# MRF49XA.net
KiCad netlist of a schematic drawn in EAGLE
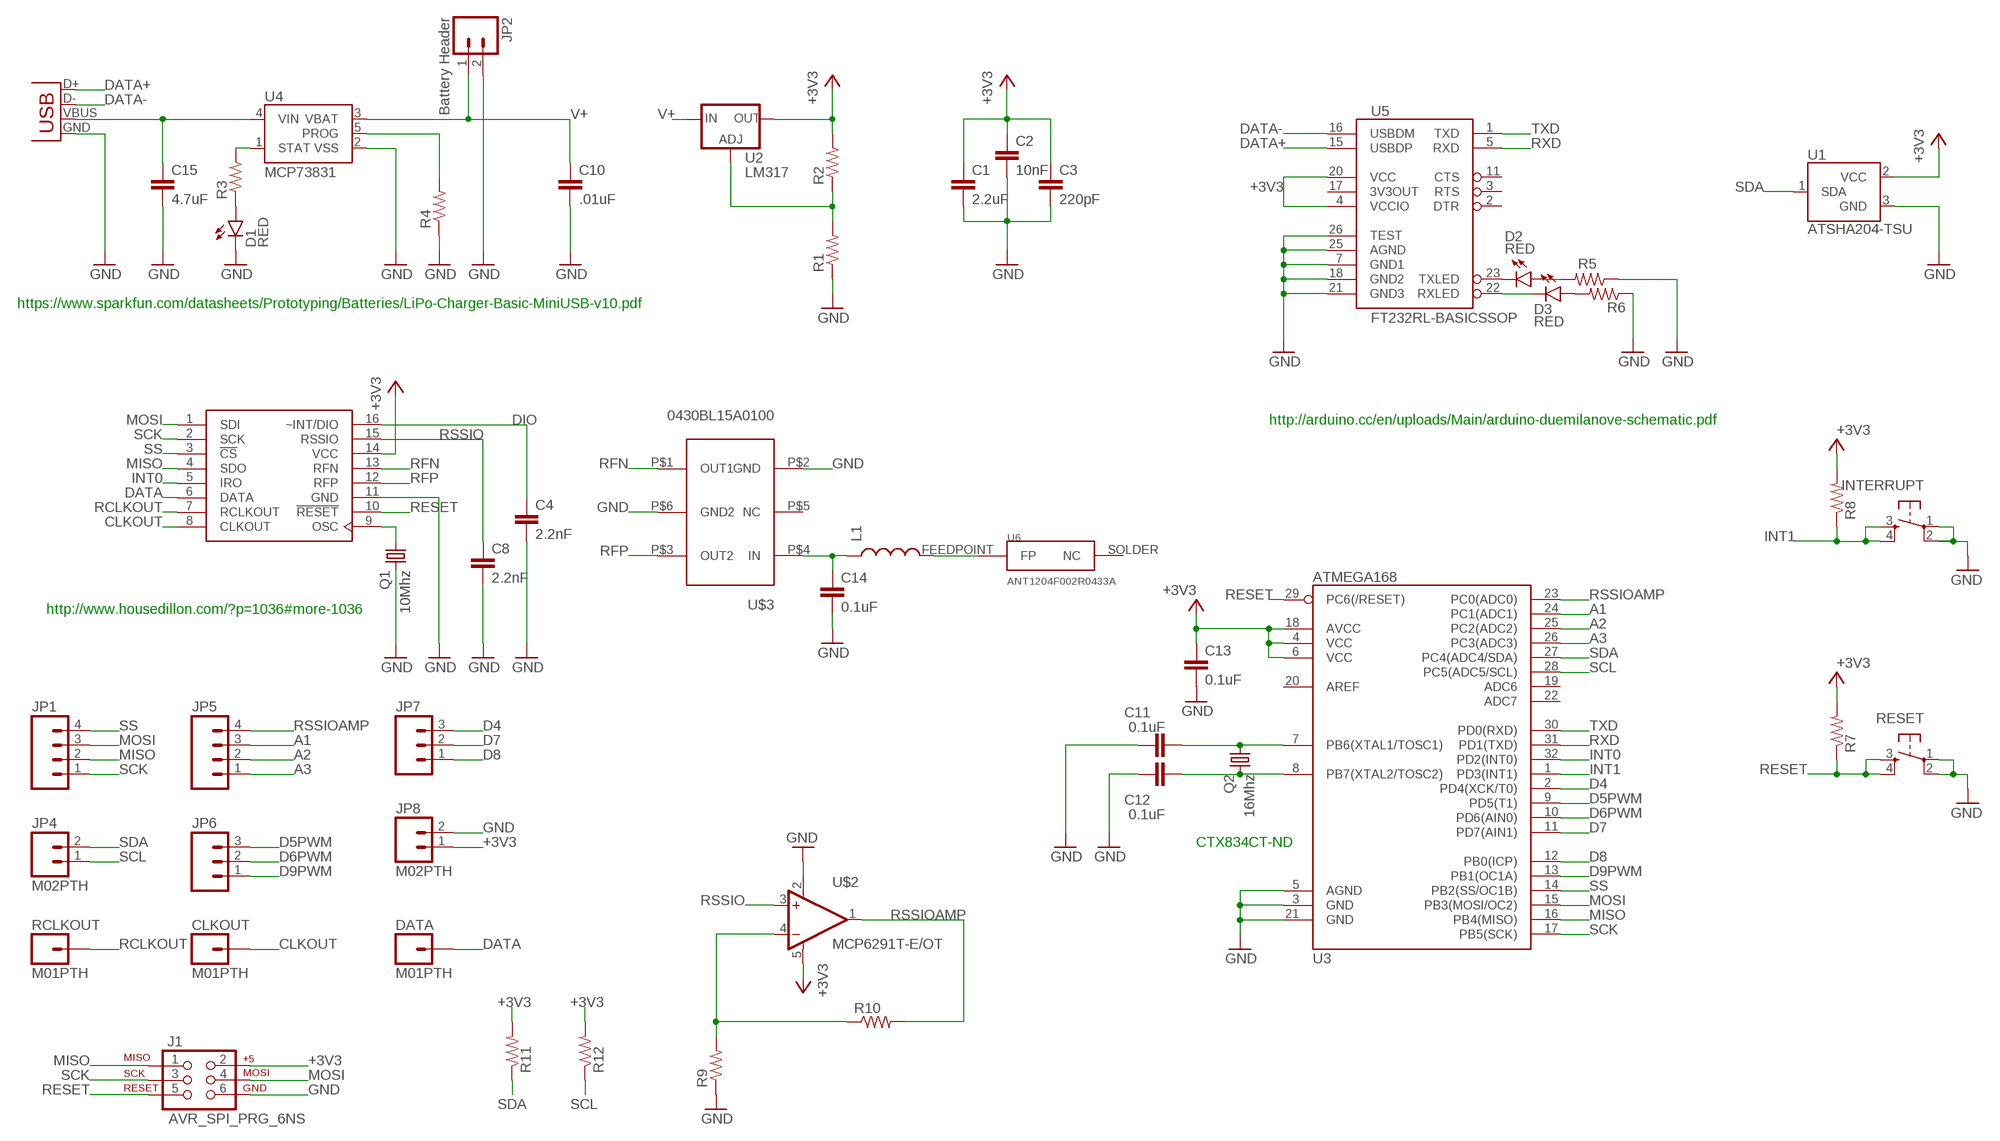
[diagram p0: schematic, sheet 1]

(export (version "E")
  (design (tool "Eeschema 10.0.6"))
  (components
    (comp (ref "C1")
      (value "2.2uF")
      (footprint "eagle-import:C3216")
      (libsource (lib "eagle-import") (part "C-EUC3216"))
    )
    (comp (ref "C2")
      (value "10nF")
      (footprint "eagle-import:C0603K")
      (libsource (lib "eagle-import") (part "C-EUC0603K"))
    )
    (comp (ref "C3")
      (value "220pF")
      (footprint "eagle-import:C0603")
      (libsource (lib "eagle-import") (part "C-EUC0603"))
    )
    (comp (ref "C4")
      (value "2.2nF")
      (footprint "eagle-import:C0603K")
      (libsource (lib "eagle-import") (part "C-EUC0603K"))
    )
    (comp (ref "C8")
      (value "2.2nF")
      (footprint "eagle-import:C0603K")
      (libsource (lib "eagle-import") (part "C-EUC0603K"))
    )
    (comp (ref "C10")
      (value ".01uF")
      (footprint "eagle-import:C3216")
      (libsource (lib "eagle-import") (part "C-EUC3216"))
    )
    (comp (ref "C11")
      (value "0.1uF")
      (footprint "eagle-import:0603-CAP")
      (libsource (lib "eagle-import") (part "0.1UF-25V-5%(0603)"))
    )
    (comp (ref "C12")
      (value "0.1uF")
      (footprint "eagle-import:0603-CAP")
      (libsource (lib "eagle-import") (part "0.1UF-25V-5%(0603)"))
    )
    (comp (ref "C13")
      (value "0.1uF")
      (footprint "eagle-import:0603-CAP")
      (libsource (lib "eagle-import") (part "0.1UF-25V-5%(0603)"))
    )
    (comp (ref "C14")
      (value "0.1uF")
      (footprint "eagle-import:0603-CAP")
      (libsource (lib "eagle-import") (part "0.1UF-25V-5%(0603)"))
    )
    (comp (ref "C15")
      (value "4.7uF")
      (footprint "eagle-import:C3216")
      (libsource (lib "eagle-import") (part "C-EUC3216"))
    )
    (comp (ref "CLKOUT")
      (value "M01PTH")
      (footprint "eagle-import:1X01")
      (libsource (lib "eagle-import") (part "M01PTH"))
    )
    (comp (ref "D1")
      (value "RED")
      (footprint "eagle-import:LED-0603")
      (libsource (lib "eagle-import") (part "LED-RED0603"))
    )
    (comp (ref "D2")
      (value "RED")
      (footprint "eagle-import:LED-0603")
      (libsource (lib "eagle-import") (part "LED-RED0603"))
    )
    (comp (ref "D3")
      (value "RED")
      (footprint "eagle-import:LED-0603")
      (libsource (lib "eagle-import") (part "LED-RED0603"))
    )
    (comp (ref "DATA")
      (value "M01PTH")
      (footprint "eagle-import:1X01")
      (libsource (lib "eagle-import") (part "M01PTH"))
    )
    (comp (ref "INTERRUPT")
      (value "TAC_SWITCHSMD")
      (footprint "eagle-import:TACTILE-SWITCH-SMD")
      (libsource (lib "eagle-import") (part "TAC_SWITCHSMD"))
    )
    (comp (ref "J1")
      (value "AVR_SPI_PRG_6NS")
      (footprint "eagle-import:2X3-NS")
      (libsource (lib "eagle-import") (part "AVR_SPI_PRG_6NS"))
    )
    (comp (ref "JP1")
      (value "M04PTH")
      (footprint "eagle-import:1X04")
      (libsource (lib "eagle-import") (part "M04PTH"))
    )
    (comp (ref "JP2")
      (value "Battery Header")
      (footprint "eagle-import:1X02_LOCK_LONGPADS")
      (libsource (lib "eagle-import") (part "M02LOCK_LONGPADS"))
    )
    (comp (ref "JP3")
      (value "USBSMD")
      (footprint "eagle-import:USB-MINIB")
      (libsource (lib "eagle-import") (part "USBSMD"))
    )
    (comp (ref "JP4")
      (value "M02PTH")
      (footprint "eagle-import:1X02")
      (libsource (lib "eagle-import") (part "M02PTH"))
    )
    (comp (ref "JP5")
      (value "M04PTH")
      (footprint "eagle-import:1X04")
      (libsource (lib "eagle-import") (part "M04PTH"))
    )
    (comp (ref "JP6")
      (value "M03PTH")
      (footprint "eagle-import:1X03")
      (libsource (lib "eagle-import") (part "M03PTH"))
    )
    (comp (ref "JP7")
      (value "M03PTH")
      (footprint "eagle-import:1X03")
      (libsource (lib "eagle-import") (part "M03PTH"))
    )
    (comp (ref "JP8")
      (value "M02PTH")
      (footprint "eagle-import:1X02")
      (libsource (lib "eagle-import") (part "M02PTH"))
    )
    (comp (ref "L1")
      (value "INDUCTOR0603")
      (footprint "eagle-import:0603")
      (libsource (lib "eagle-import") (part "INDUCTOR0603"))
    )
    (comp (ref "Q1")
      (value "10Mhz")
      (footprint "eagle-import:CTS406")
      (libsource (lib "eagle-import") (part "CRYSTALCTS406"))
    )
    (comp (ref "Q2")
      (value "16Mhz")
      (footprint "eagle-import:CTS406")
      (libsource (lib "eagle-import") (part "CRYSTALCTS406"))
    )
    (comp (ref "R1")
      (value "R-US_R0603")
      (footprint "eagle-import:R0603")
      (libsource (lib "eagle-import") (part "R-US_R0603"))
    )
    (comp (ref "R2")
      (value "R-US_R0603")
      (footprint "eagle-import:R0603")
      (libsource (lib "eagle-import") (part "R-US_R0603"))
    )
    (comp (ref "R3")
      (value "RESISTOR0603-RES")
      (footprint "eagle-import:0603-RES")
      (libsource (lib "eagle-import") (part "RESISTOR0603-RES"))
    )
    (comp (ref "R4")
      (value "RESISTOR0603-RES")
      (footprint "eagle-import:0603-RES")
      (libsource (lib "eagle-import") (part "RESISTOR0603-RES"))
    )
    (comp (ref "R5")
      (value "R-US_R0603")
      (footprint "eagle-import:R0603")
      (libsource (lib "eagle-import") (part "R-US_R0603"))
    )
    (comp (ref "R6")
      (value "R-US_R0603")
      (footprint "eagle-import:R0603")
      (libsource (lib "eagle-import") (part "R-US_R0603"))
    )
    (comp (ref "R7")
      (value "R-US_R0603")
      (footprint "eagle-import:R0603")
      (libsource (lib "eagle-import") (part "R-US_R0603"))
    )
    (comp (ref "R8")
      (value "R-US_R0603")
      (footprint "eagle-import:R0603")
      (libsource (lib "eagle-import") (part "R-US_R0603"))
    )
    (comp (ref "R9")
      (value "RESISTOR0603-RES")
      (footprint "eagle-import:0603-RES")
      (libsource (lib "eagle-import") (part "RESISTOR0603-RES"))
    )
    (comp (ref "R10")
      (value "RESISTOR0603-RES")
      (footprint "eagle-import:0603-RES")
      (libsource (lib "eagle-import") (part "RESISTOR0603-RES"))
    )
    (comp (ref "R11")
      (value "R-US_R0603")
      (footprint "eagle-import:R0603")
      (libsource (lib "eagle-import") (part "R-US_R0603"))
    )
    (comp (ref "R12")
      (value "R-US_R0603")
      (footprint "eagle-import:R0603")
      (libsource (lib "eagle-import") (part "R-US_R0603"))
    )
    (comp (ref "RCLKOUT")
      (value "M01PTH")
      (footprint "eagle-import:1X01")
      (libsource (lib "eagle-import") (part "M01PTH"))
    )
    (comp (ref "RESET")
      (value "TAC_SWITCHSMD")
      (footprint "eagle-import:TACTILE-SWITCH-SMD")
      (libsource (lib "eagle-import") (part "TAC_SWITCHSMD"))
    )
    (comp (ref "U$1")
      (value "MRF49XA")
      (footprint "eagle-import:TSSOP16")
      (libsource (lib "eagle-import") (part "MRF49XA"))
    )
    (comp (ref "U$2")
      (value "MCP6291T-E/OT")
      (footprint "eagle-import:SOT23-5")
      (libsource (lib "eagle-import") (part "MCP6291T-E/OT"))
    )
    (comp (ref "U$3")
      (value "0430BL15A0100")
      (footprint "eagle-import:0430BL15A0100")
      (libsource (lib "eagle-import") (part "0430BL15A0100"))
    )
    (comp (ref "U1")
      (value "ATSHA204-TSU")
      (footprint "eagle-import:SOT23-3")
      (libsource (lib "eagle-import") (part "ATSHA204-TSU"))
    )
    (comp (ref "U2")
      (value "LM317")
      (footprint "eagle-import:SOT223")
      (libsource (lib "eagle-import") (part "V_REG_317SMD"))
    )
    (comp (ref "U3")
      (value "ATMEGA168")
      (footprint "eagle-import:TQFP32-08")
      (libsource (lib "eagle-import") (part "ATMEGA168"))
    )
    (comp (ref "U4")
      (value "MCP73831")
      (footprint "eagle-import:SOT23-5")
      (libsource (lib "eagle-import") (part "MCP73831"))
    )
    (comp (ref "U5")
      (value "FT232RL-BASICSSOP")
      (footprint "eagle-import:SSOP28DB")
      (libsource (lib "eagle-import") (part "FT232RL-BASICSSOP"))
    )
    (comp (ref "U6")
      (value "ANT1204F002R0433A")
      (footprint "eagle-import:ANT1204F002R0433A")
      (libsource (lib "eagle-import") (part "ANT1204F002R0433A"))
    )
  )
  (nets
    (net (code "1") (name "+3V3") (class "Default")
      (node (ref "C1") (pin "1") (pinfunction "1_1") (pintype "passive"))
      (node (ref "C13") (pin "1") (pinfunction "1_1") (pintype "passive"))
      (node (ref "C2") (pin "1") (pinfunction "1_1") (pintype "passive"))
      (node (ref "C3") (pin "1") (pinfunction "1_1") (pintype "passive"))
      (node (ref "J1") (pin "2") (pinfunction "2_2") (pintype "passive"))
      (node (ref "JP8") (pin "1") (pinfunction "1_1") (pintype "passive"))
      (node (ref "R11") (pin "2") (pinfunction "2_2") (pintype "passive"))
      (node (ref "R12") (pin "2") (pinfunction "2_2") (pintype "passive"))
      (node (ref "R2") (pin "2") (pinfunction "2_2") (pintype "passive"))
      (node (ref "R7") (pin "2") (pinfunction "2_2") (pintype "passive"))
      (node (ref "R8") (pin "2") (pinfunction "2_2") (pintype "passive"))
      (node (ref "U$1") (pin "14") (pinfunction "VCC_14") (pintype "bidirectional"))
      (node (ref "U$2") (pin "5") (pinfunction "V+_5") (pintype "power_in"))
      (node (ref "U1") (pin "2") (pinfunction "VCC_2") (pintype "bidirectional"))
      (node (ref "U2") (pin "2") (pinfunction "OUT_2") (pintype "output"))
      (node (ref "U3") (pin "18") (pinfunction "AVCC_18") (pintype "bidirectional"))
      (node (ref "U3") (pin "4") (pinfunction "VCC_4") (pintype "bidirectional"))
      (node (ref "U3") (pin "6") (pinfunction "VCC_6") (pintype "bidirectional"))
      (node (ref "U5") (pin "20") (pinfunction "VCC_20") (pintype "power_in"))
      (node (ref "U5") (pin "4") (pinfunction "VCCIO_4") (pintype "power_in"))
    )
    (net (code "2") (name "/A1") (class "Default")
      (node (ref "JP5") (pin "3") (pinfunction "3_3") (pintype "passive"))
      (node (ref "U3") (pin "24") (pinfunction "PC1(ADC1)_24") (pintype "bidirectional"))
    )
    (net (code "3") (name "/A2") (class "Default")
      (node (ref "JP5") (pin "2") (pinfunction "2_2") (pintype "passive"))
      (node (ref "U3") (pin "25") (pinfunction "PC2(ADC2)_25") (pintype "bidirectional"))
    )
    (net (code "4") (name "/A3") (class "Default")
      (node (ref "JP5") (pin "1") (pinfunction "1_1") (pintype "passive"))
      (node (ref "U3") (pin "26") (pinfunction "PC3(ADC3)_26") (pintype "bidirectional"))
    )
    (net (code "5") (name "/CLKOUT") (class "Default")
      (node (ref "CLKOUT") (pin "1") (pinfunction "1_1") (pintype "passive"))
      (node (ref "U$1") (pin "8") (pinfunction "CLKOUT_8") (pintype "output"))
    )
    (net (code "6") (name "/D4") (class "Default")
      (node (ref "JP7") (pin "3") (pinfunction "3_3") (pintype "passive"))
      (node (ref "U3") (pin "2") (pinfunction "PD4(XCK/T0)_2") (pintype "bidirectional"))
    )
    (net (code "7") (name "/D5PWM") (class "Default")
      (node (ref "JP6") (pin "3") (pinfunction "3_3") (pintype "passive"))
      (node (ref "U3") (pin "9") (pinfunction "PD5(T1)_9") (pintype "bidirectional"))
    )
    (net (code "8") (name "/D6PWM") (class "Default")
      (node (ref "JP6") (pin "2") (pinfunction "2_2") (pintype "passive"))
      (node (ref "U3") (pin "10") (pinfunction "PD6(AIN0)_10") (pintype "bidirectional"))
    )
    (net (code "9") (name "/D7") (class "Default")
      (node (ref "JP7") (pin "2") (pinfunction "2_2") (pintype "passive"))
      (node (ref "U3") (pin "11") (pinfunction "PD7(AIN1)_11") (pintype "bidirectional"))
    )
    (net (code "10") (name "/D8") (class "Default")
      (node (ref "JP7") (pin "1") (pinfunction "1_1") (pintype "passive"))
      (node (ref "U3") (pin "12") (pinfunction "PB0(ICP)_12") (pintype "bidirectional"))
    )
    (net (code "11") (name "/D9PWM") (class "Default")
      (node (ref "JP6") (pin "1") (pinfunction "1_1") (pintype "passive"))
      (node (ref "U3") (pin "13") (pinfunction "PB1(OC1A)_13") (pintype "bidirectional"))
    )
    (net (code "12") (name "/DATA") (class "Default")
      (node (ref "DATA") (pin "1") (pinfunction "1_1") (pintype "passive"))
      (node (ref "U$1") (pin "6") (pinfunction "DATA_6") (pintype "bidirectional"))
    )
    (net (code "13") (name "/DATA+") (class "Default")
      (node (ref "JP3") (pin "D+") (pinfunction "D+_D+") (pintype "bidirectional"))
      (node (ref "U5") (pin "15") (pinfunction "USBDP_15") (pintype "bidirectional"))
    )
    (net (code "14") (name "/DATA-") (class "Default")
      (node (ref "JP3") (pin "D-") (pinfunction "D-_D-") (pintype "bidirectional"))
      (node (ref "U5") (pin "16") (pinfunction "USBDM_16") (pintype "bidirectional"))
    )
    (net (code "15") (name "/DIO") (class "Default")
      (node (ref "C4") (pin "1") (pinfunction "1_1") (pintype "passive"))
      (node (ref "U$1") (pin "16") (pinfunction "~{INT/DIO}_16") (pintype "bidirectional"))
    )
    (net (code "16") (name "/INT0") (class "Default")
      (node (ref "U$1") (pin "5") (pinfunction "IRO_5") (pintype "output"))
      (node (ref "U3") (pin "32") (pinfunction "PD2(INT0)_32") (pintype "bidirectional"))
    )
    (net (code "17") (name "/INT1") (class "Default")
      (node (ref "INTERRUPT") (pin "3") (pinfunction "3_3") (pintype "passive"))
      (node (ref "INTERRUPT") (pin "4") (pinfunction "4_4") (pintype "passive"))
      (node (ref "R8") (pin "1") (pinfunction "1_1") (pintype "passive"))
      (node (ref "U3") (pin "1") (pinfunction "PD3(INT1)_1") (pintype "bidirectional"))
    )
    (net (code "18") (name "/MISO") (class "Default")
      (node (ref "J1") (pin "1") (pinfunction "1_1") (pintype "passive"))
      (node (ref "JP1") (pin "2") (pinfunction "2_2") (pintype "passive"))
      (node (ref "U$1") (pin "4") (pinfunction "SDO_4") (pintype "output"))
      (node (ref "U3") (pin "16") (pinfunction "PB4(MISO)_16") (pintype "bidirectional"))
    )
    (net (code "19") (name "/MOSI") (class "Default")
      (node (ref "J1") (pin "4") (pinfunction "4_4") (pintype "passive"))
      (node (ref "JP1") (pin "3") (pinfunction "3_3") (pintype "passive"))
      (node (ref "U$1") (pin "1") (pinfunction "SDI_1") (pintype "input"))
      (node (ref "U3") (pin "15") (pinfunction "PB3(MOSI/OC2)_15") (pintype "bidirectional"))
    )
    (net (code "20") (name "/RCLKOUT") (class "Default")
      (node (ref "RCLKOUT") (pin "1") (pinfunction "1_1") (pintype "passive"))
      (node (ref "U$1") (pin "7") (pinfunction "RCLKOUT_7") (pintype "bidirectional"))
    )
    (net (code "21") (name "/RESET") (class "Default")
      (node (ref "J1") (pin "5") (pinfunction "5_5") (pintype "passive"))
      (node (ref "R7") (pin "1") (pinfunction "1_1") (pintype "passive"))
      (node (ref "RESET") (pin "3") (pinfunction "3_3") (pintype "passive"))
      (node (ref "RESET") (pin "4") (pinfunction "4_4") (pintype "passive"))
      (node (ref "U$1") (pin "10") (pinfunction "~{RESET}_10") (pintype "bidirectional"))
      (node (ref "U3") (pin "29") (pinfunction "PC6(/RESET)_29") (pintype "bidirectional"))
    )
    (net (code "22") (name "/RFN") (class "Default")
      (node (ref "U$1") (pin "13") (pinfunction "RFN_13") (pintype "bidirectional"))
      (node (ref "U$3") (pin "P$1") (pinfunction "OUT1_P$1") (pintype "bidirectional"))
    )
    (net (code "23") (name "/RFP") (class "Default")
      (node (ref "U$1") (pin "12") (pinfunction "RFP_12") (pintype "bidirectional"))
      (node (ref "U$3") (pin "P$3") (pinfunction "OUT2_P$3") (pintype "bidirectional"))
    )
    (net (code "24") (name "/RSSIO") (class "Default")
      (node (ref "C8") (pin "1") (pinfunction "1_1") (pintype "passive"))
      (node (ref "U$1") (pin "15") (pinfunction "RSSIO_15") (pintype "bidirectional"))
      (node (ref "U$2") (pin "3") (pinfunction "+IN_3") (pintype "input"))
    )
    (net (code "25") (name "/RSSIOAMP") (class "Default")
      (node (ref "JP5") (pin "4") (pinfunction "4_4") (pintype "passive"))
      (node (ref "R10") (pin "2") (pinfunction "2_2") (pintype "passive"))
      (node (ref "U$2") (pin "1") (pinfunction "OUT_1") (pintype "output"))
      (node (ref "U3") (pin "23") (pinfunction "PC0(ADC0)_23") (pintype "bidirectional"))
    )
    (net (code "26") (name "/RXD") (class "Default")
      (node (ref "U3") (pin "31") (pinfunction "PD1(TXD)_31") (pintype "bidirectional"))
      (node (ref "U5") (pin "5") (pinfunction "RXD_5") (pintype "input"))
    )
    (net (code "27") (name "/SCK") (class "Default")
      (node (ref "J1") (pin "3") (pinfunction "3_3") (pintype "passive"))
      (node (ref "JP1") (pin "1") (pinfunction "1_1") (pintype "passive"))
      (node (ref "U$1") (pin "2") (pinfunction "SCK_2") (pintype "input"))
      (node (ref "U3") (pin "17") (pinfunction "PB5(SCK)_17") (pintype "bidirectional"))
    )
    (net (code "28") (name "/SCL") (class "Default")
      (node (ref "JP4") (pin "1") (pinfunction "1_1") (pintype "passive"))
      (node (ref "R12") (pin "1") (pinfunction "1_1") (pintype "passive"))
      (node (ref "U3") (pin "28") (pinfunction "PC5(ADC5/SCL)_28") (pintype "bidirectional"))
    )
    (net (code "29") (name "/SDA") (class "Default")
      (node (ref "JP4") (pin "2") (pinfunction "2_2") (pintype "passive"))
      (node (ref "R11") (pin "1") (pinfunction "1_1") (pintype "passive"))
      (node (ref "U1") (pin "1") (pinfunction "SDA_1") (pintype "bidirectional"))
      (node (ref "U3") (pin "27") (pinfunction "PC4(ADC4/SDA)_27") (pintype "bidirectional"))
    )
    (net (code "30") (name "/SS") (class "Default")
      (node (ref "JP1") (pin "4") (pinfunction "4_4") (pintype "passive"))
      (node (ref "U$1") (pin "3") (pinfunction "~{CS}_3") (pintype "input"))
      (node (ref "U3") (pin "14") (pinfunction "PB2(SS/OC1B)_14") (pintype "bidirectional"))
    )
    (net (code "31") (name "/TXD") (class "Default")
      (node (ref "U3") (pin "30") (pinfunction "PD0(RXD)_30") (pintype "bidirectional"))
      (node (ref "U5") (pin "1") (pinfunction "TXD_1") (pintype "output"))
    )
    (net (code "32") (name "/V+") (class "Default")
      (node (ref "C10") (pin "1") (pinfunction "1_1") (pintype "passive"))
      (node (ref "JP2") (pin "1") (pinfunction "1_1") (pintype "passive"))
      (node (ref "U2") (pin "3") (pinfunction "IN_3") (pintype "input"))
      (node (ref "U4") (pin "3") (pinfunction "VBAT_3") (pintype "power_in"))
    )
    (net (code "33") (name "GND") (class "Default")
      (node (ref "C1") (pin "2") (pinfunction "2_2") (pintype "passive"))
      (node (ref "C10") (pin "2") (pinfunction "2_2") (pintype "passive"))
      (node (ref "C11") (pin "1") (pinfunction "1_1") (pintype "passive"))
      (node (ref "C12") (pin "1") (pinfunction "1_1") (pintype "passive"))
      (node (ref "C13") (pin "2") (pinfunction "2_2") (pintype "passive"))
      (node (ref "C14") (pin "2") (pinfunction "2_2") (pintype "passive"))
      (node (ref "C15") (pin "2") (pinfunction "2_2") (pintype "passive"))
      (node (ref "C2") (pin "2") (pinfunction "2_2") (pintype "passive"))
      (node (ref "C3") (pin "2") (pinfunction "2_2") (pintype "passive"))
      (node (ref "C4") (pin "2") (pinfunction "2_2") (pintype "passive"))
      (node (ref "C8") (pin "2") (pinfunction "2_2") (pintype "passive"))
      (node (ref "D1") (pin "C") (pinfunction "C_C") (pintype "passive"))
      (node (ref "INTERRUPT") (pin "1") (pinfunction "1_1") (pintype "passive"))
      (node (ref "INTERRUPT") (pin "2") (pinfunction "2_2") (pintype "passive"))
      (node (ref "J1") (pin "6") (pinfunction "6_6") (pintype "passive"))
      (node (ref "JP2") (pin "2") (pinfunction "2_2") (pintype "passive"))
      (node (ref "JP3") (pin "GND") (pinfunction "GND_GND") (pintype "bidirectional"))
      (node (ref "JP8") (pin "2") (pinfunction "2_2") (pintype "passive"))
      (node (ref "Q1") (pin "3") (pinfunction "2_3") (pintype "passive"))
      (node (ref "R1") (pin "1") (pinfunction "1_1") (pintype "passive"))
      (node (ref "R4") (pin "1") (pinfunction "1_1") (pintype "passive"))
      (node (ref "R5") (pin "1") (pinfunction "1_1") (pintype "passive"))
      (node (ref "R6") (pin "1") (pinfunction "1_1") (pintype "passive"))
      (node (ref "R9") (pin "1") (pinfunction "1_1") (pintype "passive"))
      (node (ref "RESET") (pin "1") (pinfunction "1_1") (pintype "passive"))
      (node (ref "RESET") (pin "2") (pinfunction "2_2") (pintype "passive"))
      (node (ref "U$1") (pin "11") (pinfunction "GND_11") (pintype "bidirectional"))
      (node (ref "U$2") (pin "2") (pinfunction "V-_2") (pintype "power_in"))
      (node (ref "U$3") (pin "P$2") (pinfunction "GND_P$2") (pintype "bidirectional"))
      (node (ref "U$3") (pin "P$6") (pinfunction "GND2_P$6") (pintype "bidirectional"))
      (node (ref "U1") (pin "3") (pinfunction "GND_3") (pintype "bidirectional"))
      (node (ref "U3") (pin "21") (pinfunction "GND_21") (pintype "bidirectional"))
      (node (ref "U3") (pin "3") (pinfunction "GND_3") (pintype "bidirectional"))
      (node (ref "U3") (pin "5") (pinfunction "AGND_5") (pintype "bidirectional"))
      (node (ref "U4") (pin "2") (pinfunction "VSS_2") (pintype "power_in"))
      (node (ref "U5") (pin "18") (pinfunction "GND2_18") (pintype "power_in"))
      (node (ref "U5") (pin "21") (pinfunction "GND3_21") (pintype "power_in"))
      (node (ref "U5") (pin "25") (pinfunction "AGND_25") (pintype "power_in"))
      (node (ref "U5") (pin "26") (pinfunction "TEST_26") (pintype "input"))
      (node (ref "U5") (pin "7") (pinfunction "GND1_7") (pintype "power_in"))
    )
    (net (code "34") (name "Net-(D1-PadA)") (class "Default")
      (node (ref "D1") (pin "A") (pinfunction "A_A") (pintype "passive"))
      (node (ref "R3") (pin "1") (pinfunction "1_1") (pintype "passive"))
    )
    (net (code "35") (name "Net-(D2-PadA)") (class "Default")
      (node (ref "D2") (pin "A") (pinfunction "A_A") (pintype "passive"))
      (node (ref "R5") (pin "2") (pinfunction "2_2") (pintype "passive"))
    )
    (net (code "36") (name "Net-(D3-PadA)") (class "Default")
      (node (ref "D3") (pin "A") (pinfunction "A_A") (pintype "passive"))
      (node (ref "R6") (pin "2") (pinfunction "2_2") (pintype "passive"))
    )
    (net (code "37") (name "Net-(Q2-2)") (class "Default")
      (node (ref "C12") (pin "2") (pinfunction "2_2") (pintype "passive"))
      (node (ref "Q2") (pin "3") (pinfunction "2_3") (pintype "passive"))
      (node (ref "U3") (pin "8") (pinfunction "PB7(XTAL2/TOSC2)_8") (pintype "bidirectional"))
    )
    (net (code "38") (name "Net-(U$1A-OSC)") (class "Default")
      (node (ref "Q1") (pin "1") (pinfunction "1_1") (pintype "passive"))
      (node (ref "U$1") (pin "9") (pinfunction "OSC_9") (pintype "bidirectional"))
    )
    (net (code "39") (name "Net-(U$2--IN)") (class "Default")
      (node (ref "R10") (pin "1") (pinfunction "1_1") (pintype "passive"))
      (node (ref "R9") (pin "2") (pinfunction "2_2") (pintype "passive"))
      (node (ref "U$2") (pin "4") (pinfunction "-IN_4") (pintype "input"))
    )
    (net (code "40") (name "Net-(U$3-IN)") (class "Default")
      (node (ref "C14") (pin "1") (pinfunction "1_1") (pintype "passive"))
      (node (ref "L1") (pin "1") (pinfunction "1_1") (pintype "passive"))
      (node (ref "U$3") (pin "P$4") (pinfunction "IN_P$4") (pintype "bidirectional"))
    )
    (net (code "41") (name "Net-(U2-ADJ)") (class "Default")
      (node (ref "R1") (pin "2") (pinfunction "2_2") (pintype "passive"))
      (node (ref "R2") (pin "1") (pinfunction "1_1") (pintype "passive"))
      (node (ref "U2") (pin "1") (pinfunction "ADJ_1") (pintype "input"))
    )
    (net (code "42") (name "Net-(U3-PB6(XTAL1{slash}TOSC1))") (class "Default")
      (node (ref "C11") (pin "2") (pinfunction "2_2") (pintype "passive"))
      (node (ref "Q2") (pin "1") (pinfunction "1_1") (pintype "passive"))
      (node (ref "U3") (pin "7") (pinfunction "PB6(XTAL1/TOSC1)_7") (pintype "bidirectional"))
    )
    (net (code "43") (name "Net-(U4-PROG)") (class "Default")
      (node (ref "R4") (pin "2") (pinfunction "2_2") (pintype "passive"))
      (node (ref "U4") (pin "5") (pinfunction "PROG_5") (pintype "input"))
    )
    (net (code "44") (name "Net-(U4-STAT)") (class "Default")
      (node (ref "R3") (pin "2") (pinfunction "2_2") (pintype "passive"))
      (node (ref "U4") (pin "1") (pinfunction "STAT_1") (pintype "output"))
    )
    (net (code "45") (name "Net-(U4-VIN)") (class "Default")
      (node (ref "C15") (pin "1") (pinfunction "1_1") (pintype "passive"))
      (node (ref "JP3") (pin "VBUS") (pinfunction "VBUS_VBUS") (pintype "bidirectional"))
      (node (ref "U4") (pin "4") (pinfunction "VIN_4") (pintype "power_in"))
    )
    (net (code "46") (name "Net-(U5-RXLED)") (class "Default")
      (node (ref "D3") (pin "C") (pinfunction "C_C") (pintype "passive"))
      (node (ref "U5") (pin "22") (pinfunction "RXLED_22") (pintype "bidirectional"))
    )
    (net (code "47") (name "Net-(U5-TXLED)") (class "Default")
      (node (ref "D2") (pin "C") (pinfunction "C_C") (pintype "passive"))
      (node (ref "U5") (pin "23") (pinfunction "TXLED_23") (pintype "bidirectional"))
    )
    (net (code "48") (name "Net-(U6-FP)") (class "Default")
      (node (ref "L1") (pin "2") (pinfunction "2_2") (pintype "passive"))
      (node (ref "U6") (pin "FEEDPOINT") (pinfunction "FP_FEEDPOINT") (pintype "bidirectional"))
    )
    (net (code "49") (name "unconnected-(U$3-NC-PadP$5)") (class "Default")
      (node (ref "U$3") (pin "P$5") (pinfunction "NC_P$5") (pintype "bidirectional"))
    )
    (net (code "50") (name "unconnected-(U3-ADC6-Pad19)") (class "Default")
      (node (ref "U3") (pin "19") (pinfunction "ADC6_19") (pintype "bidirectional"))
    )
    (net (code "51") (name "unconnected-(U3-ADC7-Pad22)") (class "Default")
      (node (ref "U3") (pin "22") (pinfunction "ADC7_22") (pintype "bidirectional"))
    )
    (net (code "52") (name "unconnected-(U3-AREF-Pad20)") (class "Default")
      (node (ref "U3") (pin "20") (pinfunction "AREF_20") (pintype "bidirectional"))
    )
    (net (code "53") (name "unconnected-(U5-3V3OUT-Pad17)") (class "Default")
      (node (ref "U5") (pin "17") (pinfunction "3V3OUT_17") (pintype "output"))
    )
    (net (code "54") (name "unconnected-(U5-CTS-Pad11)") (class "Default")
      (node (ref "U5") (pin "11") (pinfunction "CTS_11") (pintype "bidirectional"))
    )
    (net (code "55") (name "unconnected-(U5-DTR-Pad2)") (class "Default")
      (node (ref "U5") (pin "2") (pinfunction "DTR_2") (pintype "bidirectional"))
    )
    (net (code "56") (name "unconnected-(U5-RTS-Pad3)") (class "Default")
      (node (ref "U5") (pin "3") (pinfunction "RTS_3") (pintype "bidirectional"))
    )
    (net (code "57") (name "unconnected-(U6-NC-PadSOLDER)") (class "Default")
      (node (ref "U6") (pin "SOLDER") (pinfunction "NC_SOLDER") (pintype "no_connect"))
    )
  )
)
